# Switch_Matrix_CTRL.net
KiCad netlist of a schematic drawn in Altium Designer
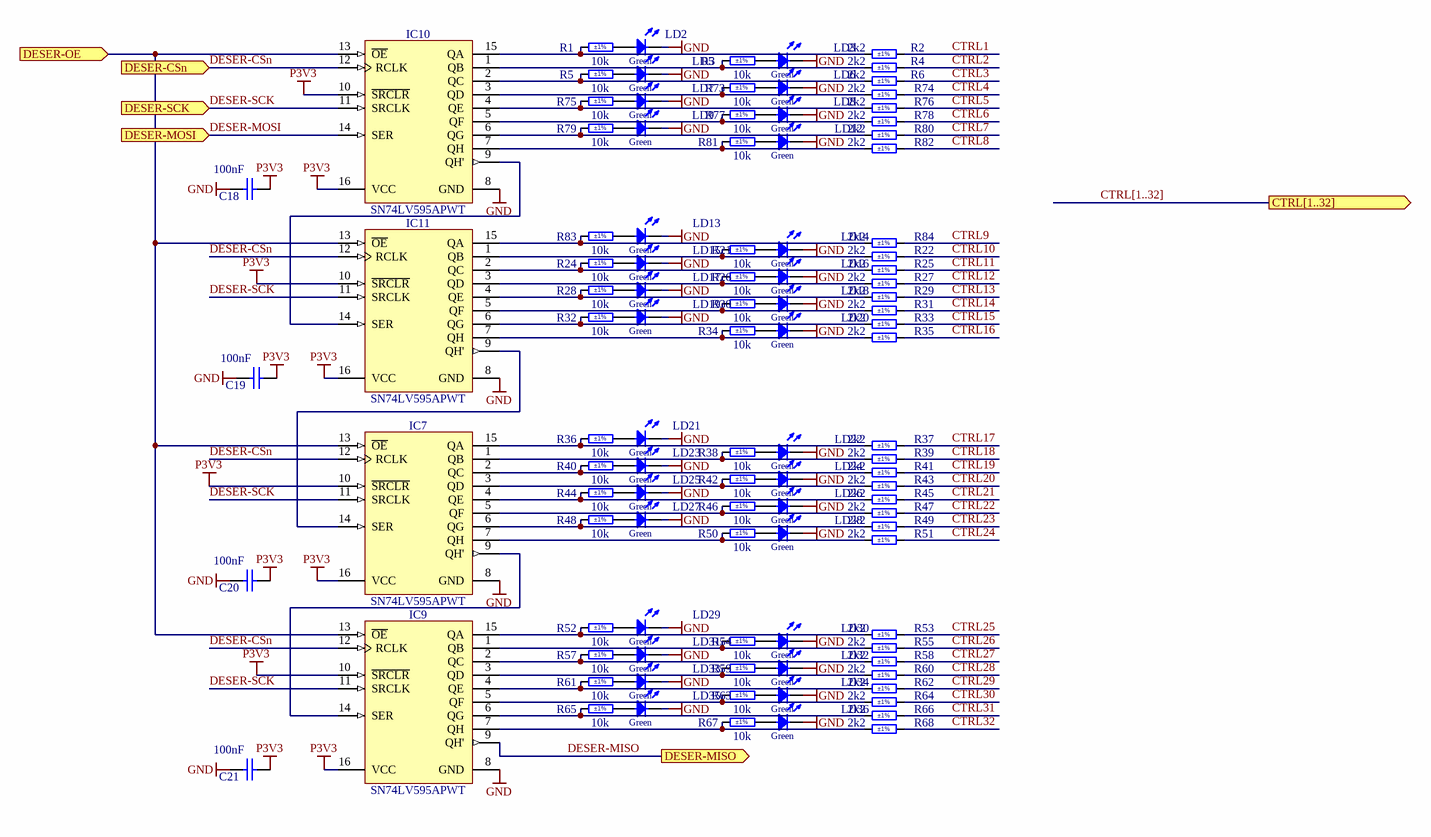
[diagram p0: Switch_Matrix_CTRL.schdoc]

(export (version "E")
  (design (tool "Eeschema 10.0.6"))
  (components
    (comp (ref "C18")
      (value "100nF")
      (footprint "CAPC1608X87N")
      (description "Non-polarised capacitor")
      (fields (field (name "PART NUMBER") "CC0603_100NF_50V_10%_X7R") (field (name "VOLTAGE") "50V"))
      (libsource (lib "Capacitors") (part "Capacitor - non polarized"))
    )
    (comp (ref "C19")
      (value "100nF")
      (footprint "CAPC1608X87N")
      (description "Non-polarised capacitor")
      (fields (field (name "PART NUMBER") "CC0603_100NF_50V_10%_X7R") (field (name "VOLTAGE") "50V"))
      (libsource (lib "Capacitors") (part "Capacitor - non polarized"))
    )
    (comp (ref "C20")
      (value "100nF")
      (footprint "CAPC1608X87N")
      (description "Non-polarised capacitor")
      (fields (field (name "PART NUMBER") "CC0603_100NF_50V_10%_X7R") (field (name "VOLTAGE") "50V"))
      (libsource (lib "Capacitors") (part "Capacitor - non polarized"))
    )
    (comp (ref "C21")
      (value "100nF")
      (footprint "CAPC1608X87N")
      (description "Non-polarised capacitor")
      (fields (field (name "PART NUMBER") "CC0603_100NF_50V_10%_X7R") (field (name "VOLTAGE") "50V"))
      (libsource (lib "Capacitors") (part "Capacitor - non polarized"))
    )
    (comp (ref "IC7")
      (value "SN74LV595APWT")
      (footprint "SOP65P640X120-16N")
      (description "8-Bit Shift Register With 3-State Output Register")
      (fields (field (name "MANUFACTURER") "TEXAS INSTRUMENTS"))
      (libsource (lib "ICs And Semiconductors") (part "74595"))
    )
    (comp (ref "IC9")
      (value "SN74LV595APWT")
      (footprint "SOP65P640X120-16N")
      (description "8-Bit Shift Register With 3-State Output Register")
      (fields (field (name "MANUFACTURER") "TEXAS INSTRUMENTS"))
      (libsource (lib "ICs And Semiconductors") (part "74595"))
    )
    (comp (ref "IC10")
      (value "SN74LV595APWT")
      (footprint "SOP65P640X120-16N")
      (description "8-Bit Shift Register With 3-State Output Register")
      (fields (field (name "MANUFACTURER") "TEXAS INSTRUMENTS"))
      (libsource (lib "ICs And Semiconductors") (part "74595"))
    )
    (comp (ref "IC11")
      (value "SN74LV595APWT")
      (footprint "SOP65P640X120-16N")
      (description "8-Bit Shift Register With 3-State Output Register")
      (fields (field (name "MANUFACTURER") "TEXAS INSTRUMENTS"))
      (libsource (lib "ICs And Semiconductors") (part "74595"))
    )
    (comp (ref "LD2")
      (value "Green")
      (footprint "LED_KINGBRIGHT_KP-1608CGCK")
      (description "LED Green 1C 2A")
      (fields
        (field (name "PART NUMBER") "LED_KINGBRIGHT_KP-1608CGCK")
        (field (name "MANUFACTURER") "KINGBRIGHT")
      )
      (libsource (lib "ICs And Semiconductors") (part "LED Green 1C 2A"))
    )
    (comp (ref "LD3")
      (value "Green")
      (footprint "LED_KINGBRIGHT_KP-1608CGCK")
      (description "LED Green 1C 2A")
      (fields
        (field (name "PART NUMBER") "LED_KINGBRIGHT_KP-1608CGCK")
        (field (name "MANUFACTURER") "KINGBRIGHT")
      )
      (libsource (lib "ICs And Semiconductors") (part "LED Green 1C 2A"))
    )
    (comp (ref "LD5")
      (value "Green")
      (footprint "LED_KINGBRIGHT_KP-1608CGCK")
      (description "LED Green 1C 2A")
      (fields
        (field (name "PART NUMBER") "LED_KINGBRIGHT_KP-1608CGCK")
        (field (name "MANUFACTURER") "KINGBRIGHT")
      )
      (libsource (lib "ICs And Semiconductors") (part "LED Green 1C 2A"))
    )
    (comp (ref "LD6")
      (value "Green")
      (footprint "LED_KINGBRIGHT_KP-1608CGCK")
      (description "LED Green 1C 2A")
      (fields
        (field (name "PART NUMBER") "LED_KINGBRIGHT_KP-1608CGCK")
        (field (name "MANUFACTURER") "KINGBRIGHT")
      )
      (libsource (lib "ICs And Semiconductors") (part "LED Green 1C 2A"))
    )
    (comp (ref "LD7")
      (value "Green")
      (footprint "LED_KINGBRIGHT_KP-1608CGCK")
      (description "LED Green 1C 2A")
      (fields
        (field (name "PART NUMBER") "LED_KINGBRIGHT_KP-1608CGCK")
        (field (name "MANUFACTURER") "KINGBRIGHT")
      )
      (libsource (lib "ICs And Semiconductors") (part "LED Green 1C 2A"))
    )
    (comp (ref "LD8")
      (value "Green")
      (footprint "LED_KINGBRIGHT_KP-1608CGCK")
      (description "LED Green 1C 2A")
      (fields
        (field (name "PART NUMBER") "LED_KINGBRIGHT_KP-1608CGCK")
        (field (name "MANUFACTURER") "KINGBRIGHT")
      )
      (libsource (lib "ICs And Semiconductors") (part "LED Green 1C 2A"))
    )
    (comp (ref "LD9")
      (value "Green")
      (footprint "LED_KINGBRIGHT_KP-1608CGCK")
      (description "LED Green 1C 2A")
      (fields
        (field (name "PART NUMBER") "LED_KINGBRIGHT_KP-1608CGCK")
        (field (name "MANUFACTURER") "KINGBRIGHT")
      )
      (libsource (lib "ICs And Semiconductors") (part "LED Green 1C 2A"))
    )
    (comp (ref "LD12")
      (value "Green")
      (footprint "LED_KINGBRIGHT_KP-1608CGCK")
      (description "LED Green 1C 2A")
      (fields
        (field (name "PART NUMBER") "LED_KINGBRIGHT_KP-1608CGCK")
        (field (name "MANUFACTURER") "KINGBRIGHT")
      )
      (libsource (lib "ICs And Semiconductors") (part "LED Green 1C 2A"))
    )
    (comp (ref "LD13")
      (value "Green")
      (footprint "LED_KINGBRIGHT_KP-1608CGCK")
      (description "LED Green 1C 2A")
      (fields
        (field (name "PART NUMBER") "LED_KINGBRIGHT_KP-1608CGCK")
        (field (name "MANUFACTURER") "KINGBRIGHT")
      )
      (libsource (lib "ICs And Semiconductors") (part "LED Green 1C 2A"))
    )
    (comp (ref "LD14")
      (value "Green")
      (footprint "LED_KINGBRIGHT_KP-1608CGCK")
      (description "LED Green 1C 2A")
      (fields
        (field (name "PART NUMBER") "LED_KINGBRIGHT_KP-1608CGCK")
        (field (name "MANUFACTURER") "KINGBRIGHT")
      )
      (libsource (lib "ICs And Semiconductors") (part "LED Green 1C 2A"))
    )
    (comp (ref "LD15")
      (value "Green")
      (footprint "LED_KINGBRIGHT_KP-1608CGCK")
      (description "LED Green 1C 2A")
      (fields
        (field (name "PART NUMBER") "LED_KINGBRIGHT_KP-1608CGCK")
        (field (name "MANUFACTURER") "KINGBRIGHT")
      )
      (libsource (lib "ICs And Semiconductors") (part "LED Green 1C 2A"))
    )
    (comp (ref "LD16")
      (value "Green")
      (footprint "LED_KINGBRIGHT_KP-1608CGCK")
      (description "LED Green 1C 2A")
      (fields
        (field (name "PART NUMBER") "LED_KINGBRIGHT_KP-1608CGCK")
        (field (name "MANUFACTURER") "KINGBRIGHT")
      )
      (libsource (lib "ICs And Semiconductors") (part "LED Green 1C 2A"))
    )
    (comp (ref "LD17")
      (value "Green")
      (footprint "LED_KINGBRIGHT_KP-1608CGCK")
      (description "LED Green 1C 2A")
      (fields
        (field (name "PART NUMBER") "LED_KINGBRIGHT_KP-1608CGCK")
        (field (name "MANUFACTURER") "KINGBRIGHT")
      )
      (libsource (lib "ICs And Semiconductors") (part "LED Green 1C 2A"))
    )
    (comp (ref "LD18")
      (value "Green")
      (footprint "LED_KINGBRIGHT_KP-1608CGCK")
      (description "LED Green 1C 2A")
      (fields
        (field (name "PART NUMBER") "LED_KINGBRIGHT_KP-1608CGCK")
        (field (name "MANUFACTURER") "KINGBRIGHT")
      )
      (libsource (lib "ICs And Semiconductors") (part "LED Green 1C 2A"))
    )
    (comp (ref "LD19")
      (value "Green")
      (footprint "LED_KINGBRIGHT_KP-1608CGCK")
      (description "LED Green 1C 2A")
      (fields
        (field (name "PART NUMBER") "LED_KINGBRIGHT_KP-1608CGCK")
        (field (name "MANUFACTURER") "KINGBRIGHT")
      )
      (libsource (lib "ICs And Semiconductors") (part "LED Green 1C 2A"))
    )
    (comp (ref "LD20")
      (value "Green")
      (footprint "LED_KINGBRIGHT_KP-1608CGCK")
      (description "LED Green 1C 2A")
      (fields
        (field (name "PART NUMBER") "LED_KINGBRIGHT_KP-1608CGCK")
        (field (name "MANUFACTURER") "KINGBRIGHT")
      )
      (libsource (lib "ICs And Semiconductors") (part "LED Green 1C 2A"))
    )
    (comp (ref "LD21")
      (value "Green")
      (footprint "LED_KINGBRIGHT_KP-1608CGCK")
      (description "LED Green 1C 2A")
      (fields
        (field (name "PART NUMBER") "LED_KINGBRIGHT_KP-1608CGCK")
        (field (name "MANUFACTURER") "KINGBRIGHT")
      )
      (libsource (lib "ICs And Semiconductors") (part "LED Green 1C 2A"))
    )
    (comp (ref "LD22")
      (value "Green")
      (footprint "LED_KINGBRIGHT_KP-1608CGCK")
      (description "LED Green 1C 2A")
      (fields
        (field (name "PART NUMBER") "LED_KINGBRIGHT_KP-1608CGCK")
        (field (name "MANUFACTURER") "KINGBRIGHT")
      )
      (libsource (lib "ICs And Semiconductors") (part "LED Green 1C 2A"))
    )
    (comp (ref "LD23")
      (value "Green")
      (footprint "LED_KINGBRIGHT_KP-1608CGCK")
      (description "LED Green 1C 2A")
      (fields
        (field (name "PART NUMBER") "LED_KINGBRIGHT_KP-1608CGCK")
        (field (name "MANUFACTURER") "KINGBRIGHT")
      )
      (libsource (lib "ICs And Semiconductors") (part "LED Green 1C 2A"))
    )
    (comp (ref "LD24")
      (value "Green")
      (footprint "LED_KINGBRIGHT_KP-1608CGCK")
      (description "LED Green 1C 2A")
      (fields
        (field (name "PART NUMBER") "LED_KINGBRIGHT_KP-1608CGCK")
        (field (name "MANUFACTURER") "KINGBRIGHT")
      )
      (libsource (lib "ICs And Semiconductors") (part "LED Green 1C 2A"))
    )
    (comp (ref "LD25")
      (value "Green")
      (footprint "LED_KINGBRIGHT_KP-1608CGCK")
      (description "LED Green 1C 2A")
      (fields
        (field (name "PART NUMBER") "LED_KINGBRIGHT_KP-1608CGCK")
        (field (name "MANUFACTURER") "KINGBRIGHT")
      )
      (libsource (lib "ICs And Semiconductors") (part "LED Green 1C 2A"))
    )
    (comp (ref "LD26")
      (value "Green")
      (footprint "LED_KINGBRIGHT_KP-1608CGCK")
      (description "LED Green 1C 2A")
      (fields
        (field (name "PART NUMBER") "LED_KINGBRIGHT_KP-1608CGCK")
        (field (name "MANUFACTURER") "KINGBRIGHT")
      )
      (libsource (lib "ICs And Semiconductors") (part "LED Green 1C 2A"))
    )
    (comp (ref "LD27")
      (value "Green")
      (footprint "LED_KINGBRIGHT_KP-1608CGCK")
      (description "LED Green 1C 2A")
      (fields
        (field (name "PART NUMBER") "LED_KINGBRIGHT_KP-1608CGCK")
        (field (name "MANUFACTURER") "KINGBRIGHT")
      )
      (libsource (lib "ICs And Semiconductors") (part "LED Green 1C 2A"))
    )
    (comp (ref "LD28")
      (value "Green")
      (footprint "LED_KINGBRIGHT_KP-1608CGCK")
      (description "LED Green 1C 2A")
      (fields
        (field (name "PART NUMBER") "LED_KINGBRIGHT_KP-1608CGCK")
        (field (name "MANUFACTURER") "KINGBRIGHT")
      )
      (libsource (lib "ICs And Semiconductors") (part "LED Green 1C 2A"))
    )
    (comp (ref "LD29")
      (value "Green")
      (footprint "LED_KINGBRIGHT_KP-1608CGCK")
      (description "LED Green 1C 2A")
      (fields
        (field (name "PART NUMBER") "LED_KINGBRIGHT_KP-1608CGCK")
        (field (name "MANUFACTURER") "KINGBRIGHT")
      )
      (libsource (lib "ICs And Semiconductors") (part "LED Green 1C 2A"))
    )
    (comp (ref "LD30")
      (value "Green")
      (footprint "LED_KINGBRIGHT_KP-1608CGCK")
      (description "LED Green 1C 2A")
      (fields
        (field (name "PART NUMBER") "LED_KINGBRIGHT_KP-1608CGCK")
        (field (name "MANUFACTURER") "KINGBRIGHT")
      )
      (libsource (lib "ICs And Semiconductors") (part "LED Green 1C 2A"))
    )
    (comp (ref "LD31")
      (value "Green")
      (footprint "LED_KINGBRIGHT_KP-1608CGCK")
      (description "LED Green 1C 2A")
      (fields
        (field (name "PART NUMBER") "LED_KINGBRIGHT_KP-1608CGCK")
        (field (name "MANUFACTURER") "KINGBRIGHT")
      )
      (libsource (lib "ICs And Semiconductors") (part "LED Green 1C 2A"))
    )
    (comp (ref "LD32")
      (value "Green")
      (footprint "LED_KINGBRIGHT_KP-1608CGCK")
      (description "LED Green 1C 2A")
      (fields
        (field (name "PART NUMBER") "LED_KINGBRIGHT_KP-1608CGCK")
        (field (name "MANUFACTURER") "KINGBRIGHT")
      )
      (libsource (lib "ICs And Semiconductors") (part "LED Green 1C 2A"))
    )
    (comp (ref "LD33")
      (value "Green")
      (footprint "LED_KINGBRIGHT_KP-1608CGCK")
      (description "LED Green 1C 2A")
      (fields
        (field (name "PART NUMBER") "LED_KINGBRIGHT_KP-1608CGCK")
        (field (name "MANUFACTURER") "KINGBRIGHT")
      )
      (libsource (lib "ICs And Semiconductors") (part "LED Green 1C 2A"))
    )
    (comp (ref "LD34")
      (value "Green")
      (footprint "LED_KINGBRIGHT_KP-1608CGCK")
      (description "LED Green 1C 2A")
      (fields
        (field (name "PART NUMBER") "LED_KINGBRIGHT_KP-1608CGCK")
        (field (name "MANUFACTURER") "KINGBRIGHT")
      )
      (libsource (lib "ICs And Semiconductors") (part "LED Green 1C 2A"))
    )
    (comp (ref "LD35")
      (value "Green")
      (footprint "LED_KINGBRIGHT_KP-1608CGCK")
      (description "LED Green 1C 2A")
      (fields
        (field (name "PART NUMBER") "LED_KINGBRIGHT_KP-1608CGCK")
        (field (name "MANUFACTURER") "KINGBRIGHT")
      )
      (libsource (lib "ICs And Semiconductors") (part "LED Green 1C 2A"))
    )
    (comp (ref "LD36")
      (value "Green")
      (footprint "LED_KINGBRIGHT_KP-1608CGCK")
      (description "LED Green 1C 2A")
      (fields
        (field (name "PART NUMBER") "LED_KINGBRIGHT_KP-1608CGCK")
        (field (name "MANUFACTURER") "KINGBRIGHT")
      )
      (libsource (lib "ICs And Semiconductors") (part "LED Green 1C 2A"))
    )
    (comp (ref "R1")
      (value "10k")
      (footprint "RESC1608X55N")
      (description "Resistor - 1%")
      (fields
        (field (name "TOLERANCE") "±1%")
        (field (name "PART NUMBER") "R0603_10K_1%_0.1W_100PPM")
        (field (name "POWER") "0.1W")
      )
      (libsource (lib "Resistors") (part "Resistor - 1%"))
    )
    (comp (ref "R2")
      (value "2k2")
      (footprint "RESC1608X55N")
      (description "Resistor - 1%")
      (fields
        (field (name "TOLERANCE") "±1%")
        (field (name "PART NUMBER") "R0603_2K2_1%_0.1W_100PPM")
        (field (name "POWER") "0.1W")
      )
      (libsource (lib "Resistors") (part "Resistor - 1%"))
    )
    (comp (ref "R3")
      (value "10k")
      (footprint "RESC1608X55N")
      (description "Resistor - 1%")
      (fields
        (field (name "TOLERANCE") "±1%")
        (field (name "PART NUMBER") "R0603_10K_1%_0.1W_100PPM")
        (field (name "POWER") "0.1W")
      )
      (libsource (lib "Resistors") (part "Resistor - 1%"))
    )
    (comp (ref "R4")
      (value "2k2")
      (footprint "RESC1608X55N")
      (description "Resistor - 1%")
      (fields
        (field (name "TOLERANCE") "±1%")
        (field (name "PART NUMBER") "R0603_2K2_1%_0.1W_100PPM")
        (field (name "POWER") "0.1W")
      )
      (libsource (lib "Resistors") (part "Resistor - 1%"))
    )
    (comp (ref "R5")
      (value "10k")
      (footprint "RESC1608X55N")
      (description "Resistor - 1%")
      (fields
        (field (name "TOLERANCE") "±1%")
        (field (name "PART NUMBER") "R0603_10K_1%_0.1W_100PPM")
        (field (name "POWER") "0.1W")
      )
      (libsource (lib "Resistors") (part "Resistor - 1%"))
    )
    (comp (ref "R6")
      (value "2k2")
      (footprint "RESC1608X55N")
      (description "Resistor - 1%")
      (fields
        (field (name "TOLERANCE") "±1%")
        (field (name "PART NUMBER") "R0603_2K2_1%_0.1W_100PPM")
        (field (name "POWER") "0.1W")
      )
      (libsource (lib "Resistors") (part "Resistor - 1%"))
    )
    (comp (ref "R21")
      (value "10k")
      (footprint "RESC1608X55N")
      (description "Resistor - 1%")
      (fields
        (field (name "TOLERANCE") "±1%")
        (field (name "PART NUMBER") "R0603_10K_1%_0.1W_100PPM")
        (field (name "POWER") "0.1W")
      )
      (libsource (lib "Resistors") (part "Resistor - 1%"))
    )
    (comp (ref "R22")
      (value "2k2")
      (footprint "RESC1608X55N")
      (description "Resistor - 1%")
      (fields
        (field (name "TOLERANCE") "±1%")
        (field (name "PART NUMBER") "R0603_2K2_1%_0.1W_100PPM")
        (field (name "POWER") "0.1W")
      )
      (libsource (lib "Resistors") (part "Resistor - 1%"))
    )
    (comp (ref "R24")
      (value "10k")
      (footprint "RESC1608X55N")
      (description "Resistor - 1%")
      (fields
        (field (name "TOLERANCE") "±1%")
        (field (name "PART NUMBER") "R0603_10K_1%_0.1W_100PPM")
        (field (name "POWER") "0.1W")
      )
      (libsource (lib "Resistors") (part "Resistor - 1%"))
    )
    (comp (ref "R25")
      (value "2k2")
      (footprint "RESC1608X55N")
      (description "Resistor - 1%")
      (fields
        (field (name "TOLERANCE") "±1%")
        (field (name "PART NUMBER") "R0603_2K2_1%_0.1W_100PPM")
        (field (name "POWER") "0.1W")
      )
      (libsource (lib "Resistors") (part "Resistor - 1%"))
    )
    (comp (ref "R26")
      (value "10k")
      (footprint "RESC1608X55N")
      (description "Resistor - 1%")
      (fields
        (field (name "TOLERANCE") "±1%")
        (field (name "PART NUMBER") "R0603_10K_1%_0.1W_100PPM")
        (field (name "POWER") "0.1W")
      )
      (libsource (lib "Resistors") (part "Resistor - 1%"))
    )
    (comp (ref "R27")
      (value "2k2")
      (footprint "RESC1608X55N")
      (description "Resistor - 1%")
      (fields
        (field (name "TOLERANCE") "±1%")
        (field (name "PART NUMBER") "R0603_2K2_1%_0.1W_100PPM")
        (field (name "POWER") "0.1W")
      )
      (libsource (lib "Resistors") (part "Resistor - 1%"))
    )
    (comp (ref "R28")
      (value "10k")
      (footprint "RESC1608X55N")
      (description "Resistor - 1%")
      (fields
        (field (name "TOLERANCE") "±1%")
        (field (name "PART NUMBER") "R0603_10K_1%_0.1W_100PPM")
        (field (name "POWER") "0.1W")
      )
      (libsource (lib "Resistors") (part "Resistor - 1%"))
    )
    (comp (ref "R29")
      (value "2k2")
      (footprint "RESC1608X55N")
      (description "Resistor - 1%")
      (fields
        (field (name "TOLERANCE") "±1%")
        (field (name "PART NUMBER") "R0603_2K2_1%_0.1W_100PPM")
        (field (name "POWER") "0.1W")
      )
      (libsource (lib "Resistors") (part "Resistor - 1%"))
    )
    (comp (ref "R30")
      (value "10k")
      (footprint "RESC1608X55N")
      (description "Resistor - 1%")
      (fields
        (field (name "TOLERANCE") "±1%")
        (field (name "PART NUMBER") "R0603_10K_1%_0.1W_100PPM")
        (field (name "POWER") "0.1W")
      )
      (libsource (lib "Resistors") (part "Resistor - 1%"))
    )
    (comp (ref "R31")
      (value "2k2")
      (footprint "RESC1608X55N")
      (description "Resistor - 1%")
      (fields
        (field (name "TOLERANCE") "±1%")
        (field (name "PART NUMBER") "R0603_2K2_1%_0.1W_100PPM")
        (field (name "POWER") "0.1W")
      )
      (libsource (lib "Resistors") (part "Resistor - 1%"))
    )
    (comp (ref "R32")
      (value "10k")
      (footprint "RESC1608X55N")
      (description "Resistor - 1%")
      (fields
        (field (name "TOLERANCE") "±1%")
        (field (name "PART NUMBER") "R0603_10K_1%_0.1W_100PPM")
        (field (name "POWER") "0.1W")
      )
      (libsource (lib "Resistors") (part "Resistor - 1%"))
    )
    (comp (ref "R33")
      (value "2k2")
      (footprint "RESC1608X55N")
      (description "Resistor - 1%")
      (fields
        (field (name "TOLERANCE") "±1%")
        (field (name "PART NUMBER") "R0603_2K2_1%_0.1W_100PPM")
        (field (name "POWER") "0.1W")
      )
      (libsource (lib "Resistors") (part "Resistor - 1%"))
    )
    (comp (ref "R34")
      (value "10k")
      (footprint "RESC1608X55N")
      (description "Resistor - 1%")
      (fields
        (field (name "TOLERANCE") "±1%")
        (field (name "PART NUMBER") "R0603_10K_1%_0.1W_100PPM")
        (field (name "POWER") "0.1W")
      )
      (libsource (lib "Resistors") (part "Resistor - 1%"))
    )
    (comp (ref "R35")
      (value "2k2")
      (footprint "RESC1608X55N")
      (description "Resistor - 1%")
      (fields
        (field (name "TOLERANCE") "±1%")
        (field (name "PART NUMBER") "R0603_2K2_1%_0.1W_100PPM")
        (field (name "POWER") "0.1W")
      )
      (libsource (lib "Resistors") (part "Resistor - 1%"))
    )
    (comp (ref "R36")
      (value "10k")
      (footprint "RESC1608X55N")
      (description "Resistor - 1%")
      (fields
        (field (name "TOLERANCE") "±1%")
        (field (name "PART NUMBER") "R0603_10K_1%_0.1W_100PPM")
        (field (name "POWER") "0.1W")
      )
      (libsource (lib "Resistors") (part "Resistor - 1%"))
    )
    (comp (ref "R37")
      (value "2k2")
      (footprint "RESC1608X55N")
      (description "Resistor - 1%")
      (fields
        (field (name "TOLERANCE") "±1%")
        (field (name "PART NUMBER") "R0603_2K2_1%_0.1W_100PPM")
        (field (name "POWER") "0.1W")
      )
      (libsource (lib "Resistors") (part "Resistor - 1%"))
    )
    (comp (ref "R38")
      (value "10k")
      (footprint "RESC1608X55N")
      (description "Resistor - 1%")
      (fields
        (field (name "TOLERANCE") "±1%")
        (field (name "PART NUMBER") "R0603_10K_1%_0.1W_100PPM")
        (field (name "POWER") "0.1W")
      )
      (libsource (lib "Resistors") (part "Resistor - 1%"))
    )
    (comp (ref "R39")
      (value "2k2")
      (footprint "RESC1608X55N")
      (description "Resistor - 1%")
      (fields
        (field (name "TOLERANCE") "±1%")
        (field (name "PART NUMBER") "R0603_2K2_1%_0.1W_100PPM")
        (field (name "POWER") "0.1W")
      )
      (libsource (lib "Resistors") (part "Resistor - 1%"))
    )
    (comp (ref "R40")
      (value "10k")
      (footprint "RESC1608X55N")
      (description "Resistor - 1%")
      (fields
        (field (name "TOLERANCE") "±1%")
        (field (name "PART NUMBER") "R0603_10K_1%_0.1W_100PPM")
        (field (name "POWER") "0.1W")
      )
      (libsource (lib "Resistors") (part "Resistor - 1%"))
    )
    (comp (ref "R41")
      (value "2k2")
      (footprint "RESC1608X55N")
      (description "Resistor - 1%")
      (fields
        (field (name "TOLERANCE") "±1%")
        (field (name "PART NUMBER") "R0603_2K2_1%_0.1W_100PPM")
        (field (name "POWER") "0.1W")
      )
      (libsource (lib "Resistors") (part "Resistor - 1%"))
    )
    (comp (ref "R42")
      (value "10k")
      (footprint "RESC1608X55N")
      (description "Resistor - 1%")
      (fields
        (field (name "TOLERANCE") "±1%")
        (field (name "PART NUMBER") "R0603_10K_1%_0.1W_100PPM")
        (field (name "POWER") "0.1W")
      )
      (libsource (lib "Resistors") (part "Resistor - 1%"))
    )
    (comp (ref "R43")
      (value "2k2")
      (footprint "RESC1608X55N")
      (description "Resistor - 1%")
      (fields
        (field (name "TOLERANCE") "±1%")
        (field (name "PART NUMBER") "R0603_2K2_1%_0.1W_100PPM")
        (field (name "POWER") "0.1W")
      )
      (libsource (lib "Resistors") (part "Resistor - 1%"))
    )
    (comp (ref "R44")
      (value "10k")
      (footprint "RESC1608X55N")
      (description "Resistor - 1%")
      (fields
        (field (name "TOLERANCE") "±1%")
        (field (name "PART NUMBER") "R0603_10K_1%_0.1W_100PPM")
        (field (name "POWER") "0.1W")
      )
      (libsource (lib "Resistors") (part "Resistor - 1%"))
    )
    (comp (ref "R45")
      (value "2k2")
      (footprint "RESC1608X55N")
      (description "Resistor - 1%")
      (fields
        (field (name "TOLERANCE") "±1%")
        (field (name "PART NUMBER") "R0603_2K2_1%_0.1W_100PPM")
        (field (name "POWER") "0.1W")
      )
      (libsource (lib "Resistors") (part "Resistor - 1%"))
    )
    (comp (ref "R46")
      (value "10k")
      (footprint "RESC1608X55N")
      (description "Resistor - 1%")
      (fields
        (field (name "TOLERANCE") "±1%")
        (field (name "PART NUMBER") "R0603_10K_1%_0.1W_100PPM")
        (field (name "POWER") "0.1W")
      )
      (libsource (lib "Resistors") (part "Resistor - 1%"))
    )
    (comp (ref "R47")
      (value "2k2")
      (footprint "RESC1608X55N")
      (description "Resistor - 1%")
      (fields
        (field (name "TOLERANCE") "±1%")
        (field (name "PART NUMBER") "R0603_2K2_1%_0.1W_100PPM")
        (field (name "POWER") "0.1W")
      )
      (libsource (lib "Resistors") (part "Resistor - 1%"))
    )
    (comp (ref "R48")
      (value "10k")
      (footprint "RESC1608X55N")
      (description "Resistor - 1%")
      (fields
        (field (name "TOLERANCE") "±1%")
        (field (name "PART NUMBER") "R0603_10K_1%_0.1W_100PPM")
        (field (name "POWER") "0.1W")
      )
      (libsource (lib "Resistors") (part "Resistor - 1%"))
    )
    (comp (ref "R49")
      (value "2k2")
      (footprint "RESC1608X55N")
      (description "Resistor - 1%")
      (fields
        (field (name "TOLERANCE") "±1%")
        (field (name "PART NUMBER") "R0603_2K2_1%_0.1W_100PPM")
        (field (name "POWER") "0.1W")
      )
      (libsource (lib "Resistors") (part "Resistor - 1%"))
    )
    (comp (ref "R50")
      (value "10k")
      (footprint "RESC1608X55N")
      (description "Resistor - 1%")
      (fields
        (field (name "TOLERANCE") "±1%")
        (field (name "PART NUMBER") "R0603_10K_1%_0.1W_100PPM")
        (field (name "POWER") "0.1W")
      )
      (libsource (lib "Resistors") (part "Resistor - 1%"))
    )
    (comp (ref "R51")
      (value "2k2")
      (footprint "RESC1608X55N")
      (description "Resistor - 1%")
      (fields
        (field (name "TOLERANCE") "±1%")
        (field (name "PART NUMBER") "R0603_2K2_1%_0.1W_100PPM")
        (field (name "POWER") "0.1W")
      )
      (libsource (lib "Resistors") (part "Resistor - 1%"))
    )
    (comp (ref "R52")
      (value "10k")
      (footprint "RESC1608X55N")
      (description "Resistor - 1%")
      (fields
        (field (name "TOLERANCE") "±1%")
        (field (name "PART NUMBER") "R0603_10K_1%_0.1W_100PPM")
        (field (name "POWER") "0.1W")
      )
      (libsource (lib "Resistors") (part "Resistor - 1%"))
    )
    (comp (ref "R53")
      (value "2k2")
      (footprint "RESC1608X55N")
      (description "Resistor - 1%")
      (fields
        (field (name "TOLERANCE") "±1%")
        (field (name "PART NUMBER") "R0603_2K2_1%_0.1W_100PPM")
        (field (name "POWER") "0.1W")
      )
      (libsource (lib "Resistors") (part "Resistor - 1%"))
    )
    (comp (ref "R54")
      (value "10k")
      (footprint "RESC1608X55N")
      (description "Resistor - 1%")
      (fields
        (field (name "TOLERANCE") "±1%")
        (field (name "PART NUMBER") "R0603_10K_1%_0.1W_100PPM")
        (field (name "POWER") "0.1W")
      )
      (libsource (lib "Resistors") (part "Resistor - 1%"))
    )
    (comp (ref "R55")
      (value "2k2")
      (footprint "RESC1608X55N")
      (description "Resistor - 1%")
      (fields
        (field (name "TOLERANCE") "±1%")
        (field (name "PART NUMBER") "R0603_2K2_1%_0.1W_100PPM")
        (field (name "POWER") "0.1W")
      )
      (libsource (lib "Resistors") (part "Resistor - 1%"))
    )
    (comp (ref "R57")
      (value "10k")
      (footprint "RESC1608X55N")
      (description "Resistor - 1%")
      (fields
        (field (name "TOLERANCE") "±1%")
        (field (name "PART NUMBER") "R0603_10K_1%_0.1W_100PPM")
        (field (name "POWER") "0.1W")
      )
      (libsource (lib "Resistors") (part "Resistor - 1%"))
    )
    (comp (ref "R58")
      (value "2k2")
      (footprint "RESC1608X55N")
      (description "Resistor - 1%")
      (fields
        (field (name "TOLERANCE") "±1%")
        (field (name "PART NUMBER") "R0603_2K2_1%_0.1W_100PPM")
        (field (name "POWER") "0.1W")
      )
      (libsource (lib "Resistors") (part "Resistor - 1%"))
    )
    (comp (ref "R59")
      (value "10k")
      (footprint "RESC1608X55N")
      (description "Resistor - 1%")
      (fields
        (field (name "TOLERANCE") "±1%")
        (field (name "PART NUMBER") "R0603_10K_1%_0.1W_100PPM")
        (field (name "POWER") "0.1W")
      )
      (libsource (lib "Resistors") (part "Resistor - 1%"))
    )
    (comp (ref "R60")
      (value "2k2")
      (footprint "RESC1608X55N")
      (description "Resistor - 1%")
      (fields
        (field (name "TOLERANCE") "±1%")
        (field (name "PART NUMBER") "R0603_2K2_1%_0.1W_100PPM")
        (field (name "POWER") "0.1W")
      )
      (libsource (lib "Resistors") (part "Resistor - 1%"))
    )
    (comp (ref "R61")
      (value "10k")
      (footprint "RESC1608X55N")
      (description "Resistor - 1%")
      (fields
        (field (name "TOLERANCE") "±1%")
        (field (name "PART NUMBER") "R0603_10K_1%_0.1W_100PPM")
        (field (name "POWER") "0.1W")
      )
      (libsource (lib "Resistors") (part "Resistor - 1%"))
    )
    (comp (ref "R62")
      (value "2k2")
      (footprint "RESC1608X55N")
      (description "Resistor - 1%")
      (fields
        (field (name "TOLERANCE") "±1%")
        (field (name "PART NUMBER") "R0603_2K2_1%_0.1W_100PPM")
        (field (name "POWER") "0.1W")
      )
      (libsource (lib "Resistors") (part "Resistor - 1%"))
    )
    (comp (ref "R63")
      (value "10k")
      (footprint "RESC1608X55N")
      (description "Resistor - 1%")
      (fields
        (field (name "TOLERANCE") "±1%")
        (field (name "PART NUMBER") "R0603_10K_1%_0.1W_100PPM")
        (field (name "POWER") "0.1W")
      )
      (libsource (lib "Resistors") (part "Resistor - 1%"))
    )
    (comp (ref "R64")
      (value "2k2")
      (footprint "RESC1608X55N")
      (description "Resistor - 1%")
      (fields
        (field (name "TOLERANCE") "±1%")
        (field (name "PART NUMBER") "R0603_2K2_1%_0.1W_100PPM")
        (field (name "POWER") "0.1W")
      )
      (libsource (lib "Resistors") (part "Resistor - 1%"))
    )
    (comp (ref "R65")
      (value "10k")
      (footprint "RESC1608X55N")
      (description "Resistor - 1%")
      (fields
        (field (name "TOLERANCE") "±1%")
        (field (name "PART NUMBER") "R0603_10K_1%_0.1W_100PPM")
        (field (name "POWER") "0.1W")
      )
      (libsource (lib "Resistors") (part "Resistor - 1%"))
    )
    (comp (ref "R66")
      (value "2k2")
      (footprint "RESC1608X55N")
      (description "Resistor - 1%")
      (fields
        (field (name "TOLERANCE") "±1%")
        (field (name "PART NUMBER") "R0603_2K2_1%_0.1W_100PPM")
        (field (name "POWER") "0.1W")
      )
      (libsource (lib "Resistors") (part "Resistor - 1%"))
    )
    (comp (ref "R67")
      (value "10k")
      (footprint "RESC1608X55N")
      (description "Resistor - 1%")
      (fields
        (field (name "TOLERANCE") "±1%")
        (field (name "PART NUMBER") "R0603_10K_1%_0.1W_100PPM")
        (field (name "POWER") "0.1W")
      )
      (libsource (lib "Resistors") (part "Resistor - 1%"))
    )
    (comp (ref "R68")
      (value "2k2")
      (footprint "RESC1608X55N")
      (description "Resistor - 1%")
      (fields
        (field (name "TOLERANCE") "±1%")
        (field (name "PART NUMBER") "R0603_2K2_1%_0.1W_100PPM")
        (field (name "POWER") "0.1W")
      )
      (libsource (lib "Resistors") (part "Resistor - 1%"))
    )
    (comp (ref "R73")
      (value "10k")
      (footprint "RESC1608X55N")
      (description "Resistor - 1%")
      (fields
        (field (name "TOLERANCE") "±1%")
        (field (name "PART NUMBER") "R0603_10K_1%_0.1W_100PPM")
        (field (name "POWER") "0.1W")
      )
      (libsource (lib "Resistors") (part "Resistor - 1%"))
    )
    (comp (ref "R74")
      (value "2k2")
      (footprint "RESC1608X55N")
      (description "Resistor - 1%")
      (fields
        (field (name "TOLERANCE") "±1%")
        (field (name "PART NUMBER") "R0603_2K2_1%_0.1W_100PPM")
        (field (name "POWER") "0.1W")
      )
      (libsource (lib "Resistors") (part "Resistor - 1%"))
    )
    (comp (ref "R75")
      (value "10k")
      (footprint "RESC1608X55N")
      (description "Resistor - 1%")
      (fields
        (field (name "TOLERANCE") "±1%")
        (field (name "PART NUMBER") "R0603_10K_1%_0.1W_100PPM")
        (field (name "POWER") "0.1W")
      )
      (libsource (lib "Resistors") (part "Resistor - 1%"))
    )
    (comp (ref "R76")
      (value "2k2")
      (footprint "RESC1608X55N")
      (description "Resistor - 1%")
      (fields
        (field (name "TOLERANCE") "±1%")
        (field (name "PART NUMBER") "R0603_2K2_1%_0.1W_100PPM")
        (field (name "POWER") "0.1W")
      )
      (libsource (lib "Resistors") (part "Resistor - 1%"))
    )
    (comp (ref "R77")
      (value "10k")
      (footprint "RESC1608X55N")
      (description "Resistor - 1%")
      (fields
        (field (name "TOLERANCE") "±1%")
        (field (name "PART NUMBER") "R0603_10K_1%_0.1W_100PPM")
        (field (name "POWER") "0.1W")
      )
      (libsource (lib "Resistors") (part "Resistor - 1%"))
    )
    (comp (ref "R78")
      (value "2k2")
      (footprint "RESC1608X55N")
      (description "Resistor - 1%")
      (fields
        (field (name "TOLERANCE") "±1%")
        (field (name "PART NUMBER") "R0603_2K2_1%_0.1W_100PPM")
        (field (name "POWER") "0.1W")
      )
      (libsource (lib "Resistors") (part "Resistor - 1%"))
    )
    (comp (ref "R79")
      (value "10k")
      (footprint "RESC1608X55N")
      (description "Resistor - 1%")
      (fields
        (field (name "TOLERANCE") "±1%")
        (field (name "PART NUMBER") "R0603_10K_1%_0.1W_100PPM")
        (field (name "POWER") "0.1W")
      )
      (libsource (lib "Resistors") (part "Resistor - 1%"))
    )
    (comp (ref "R80")
      (value "2k2")
      (footprint "RESC1608X55N")
      (description "Resistor - 1%")
      (fields
        (field (name "TOLERANCE") "±1%")
        (field (name "PART NUMBER") "R0603_2K2_1%_0.1W_100PPM")
        (field (name "POWER") "0.1W")
      )
      (libsource (lib "Resistors") (part "Resistor - 1%"))
    )
    (comp (ref "R81")
      (value "10k")
      (footprint "RESC1608X55N")
      (description "Resistor - 1%")
      (fields
        (field (name "TOLERANCE") "±1%")
        (field (name "PART NUMBER") "R0603_10K_1%_0.1W_100PPM")
        (field (name "POWER") "0.1W")
      )
      (libsource (lib "Resistors") (part "Resistor - 1%"))
    )
    (comp (ref "R82")
      (value "2k2")
      (footprint "RESC1608X55N")
      (description "Resistor - 1%")
      (fields
        (field (name "TOLERANCE") "±1%")
        (field (name "PART NUMBER") "R0603_2K2_1%_0.1W_100PPM")
        (field (name "POWER") "0.1W")
      )
      (libsource (lib "Resistors") (part "Resistor - 1%"))
    )
    (comp (ref "R83")
      (value "10k")
      (footprint "RESC1608X55N")
      (description "Resistor - 1%")
      (fields
        (field (name "TOLERANCE") "±1%")
        (field (name "PART NUMBER") "R0603_10K_1%_0.1W_100PPM")
        (field (name "POWER") "0.1W")
      )
      (libsource (lib "Resistors") (part "Resistor - 1%"))
    )
    (comp (ref "R84")
      (value "2k2")
      (footprint "RESC1608X55N")
      (description "Resistor - 1%")
      (fields
        (field (name "TOLERANCE") "±1%")
        (field (name "PART NUMBER") "R0603_2K2_1%_0.1W_100PPM")
        (field (name "POWER") "0.1W")
      )
      (libsource (lib "Resistors") (part "Resistor - 1%"))
    )
  )
  (nets
    (net (code "1") (name "/CTRL1") (class "Default")
      (node (ref "R2") (pin "2") (pinfunction "2_2") (pintype "passive"))
    )
    (net (code "2") (name "/CTRL2") (class "Default")
      (node (ref "R4") (pin "2") (pinfunction "2_2") (pintype "passive"))
    )
    (net (code "3") (name "/CTRL3") (class "Default")
      (node (ref "R6") (pin "2") (pinfunction "2_2") (pintype "passive"))
    )
    (net (code "4") (name "/CTRL4") (class "Default")
      (node (ref "R74") (pin "2") (pinfunction "2_2") (pintype "passive"))
    )
    (net (code "5") (name "/CTRL5") (class "Default")
      (node (ref "R76") (pin "2") (pinfunction "2_2") (pintype "passive"))
    )
    (net (code "6") (name "/CTRL6") (class "Default")
      (node (ref "R78") (pin "2") (pinfunction "2_2") (pintype "passive"))
    )
    (net (code "7") (name "/CTRL7") (class "Default")
      (node (ref "R80") (pin "2") (pinfunction "2_2") (pintype "passive"))
    )
    (net (code "8") (name "/CTRL8") (class "Default")
      (node (ref "R82") (pin "2") (pinfunction "2_2") (pintype "passive"))
    )
    (net (code "9") (name "/CTRL9") (class "Default")
      (node (ref "R84") (pin "2") (pinfunction "2_2") (pintype "passive"))
    )
    (net (code "10") (name "/CTRL10") (class "Default")
      (node (ref "R22") (pin "2") (pinfunction "2_2") (pintype "passive"))
    )
    (net (code "11") (name "/CTRL11") (class "Default")
      (node (ref "R25") (pin "2") (pinfunction "2_2") (pintype "passive"))
    )
    (net (code "12") (name "/CTRL12") (class "Default")
      (node (ref "R27") (pin "2") (pinfunction "2_2") (pintype "passive"))
    )
    (net (code "13") (name "/CTRL13") (class "Default")
      (node (ref "R29") (pin "2") (pinfunction "2_2") (pintype "passive"))
    )
    (net (code "14") (name "/CTRL14") (class "Default")
      (node (ref "R31") (pin "2") (pinfunction "2_2") (pintype "passive"))
    )
    (net (code "15") (name "/CTRL15") (class "Default")
      (node (ref "R33") (pin "2") (pinfunction "2_2") (pintype "passive"))
    )
    (net (code "16") (name "/CTRL16") (class "Default")
      (node (ref "R35") (pin "2") (pinfunction "2_2") (pintype "passive"))
    )
    (net (code "17") (name "/CTRL17") (class "Default")
      (node (ref "R37") (pin "2") (pinfunction "2_2") (pintype "passive"))
    )
    (net (code "18") (name "/CTRL18") (class "Default")
      (node (ref "R39") (pin "2") (pinfunction "2_2") (pintype "passive"))
    )
    (net (code "19") (name "/CTRL19") (class "Default")
      (node (ref "R41") (pin "2") (pinfunction "2_2") (pintype "passive"))
    )
    (net (code "20") (name "/CTRL20") (class "Default")
      (node (ref "R43") (pin "2") (pinfunction "2_2") (pintype "passive"))
    )
    (net (code "21") (name "/CTRL21") (class "Default")
      (node (ref "R45") (pin "2") (pinfunction "2_2") (pintype "passive"))
    )
    (net (code "22") (name "/CTRL22") (class "Default")
      (node (ref "R47") (pin "2") (pinfunction "2_2") (pintype "passive"))
    )
    (net (code "23") (name "/CTRL23") (class "Default")
      (node (ref "R49") (pin "2") (pinfunction "2_2") (pintype "passive"))
    )
    (net (code "24") (name "/CTRL24") (class "Default")
      (node (ref "R51") (pin "2") (pinfunction "2_2") (pintype "passive"))
    )
    (net (code "25") (name "/CTRL25") (class "Default")
      (node (ref "R53") (pin "2") (pinfunction "2_2") (pintype "passive"))
    )
    (net (code "26") (name "/CTRL26") (class "Default")
      (node (ref "R55") (pin "2") (pinfunction "2_2") (pintype "passive"))
    )
    (net (code "27") (name "/CTRL27") (class "Default")
      (node (ref "R58") (pin "2") (pinfunction "2_2") (pintype "passive"))
    )
    (net (code "28") (name "/CTRL28") (class "Default")
      (node (ref "R60") (pin "2") (pinfunction "2_2") (pintype "passive"))
    )
    (net (code "29") (name "/CTRL29") (class "Default")
      (node (ref "R62") (pin "2") (pinfunction "2_2") (pintype "passive"))
    )
    (net (code "30") (name "/CTRL30") (class "Default")
      (node (ref "R64") (pin "2") (pinfunction "2_2") (pintype "passive"))
    )
    (net (code "31") (name "/CTRL31") (class "Default")
      (node (ref "R66") (pin "2") (pinfunction "2_2") (pintype "passive"))
    )
    (net (code "32") (name "/CTRL32") (class "Default")
      (node (ref "R68") (pin "2") (pinfunction "2_2") (pintype "passive"))
    )
    (net (code "34") (name "/DESER-CSn") (class "Default")
      (node (ref "IC10") (pin "12") (pinfunction "RCLK_12") (pintype "input"))
      (node (ref "IC11") (pin "12") (pinfunction "RCLK_12") (pintype "input"))
      (node (ref "IC7") (pin "12") (pinfunction "RCLK_12") (pintype "input"))
      (node (ref "IC9") (pin "12") (pinfunction "RCLK_12") (pintype "input"))
    )
    (net (code "35") (name "/DESER-MISO") (class "Default")
      (node (ref "IC9") (pin "9") (pinfunction "QH'_9") (pintype "output"))
    )
    (net (code "36") (name "/DESER-MOSI") (class "Default")
      (node (ref "IC10") (pin "14") (pinfunction "SER_14") (pintype "input"))
    )
    (net (code "37") (name "/DESER-OE") (class "Default")
      (node (ref "IC10") (pin "13") (pinfunction "~{OE}_13") (pintype "input"))
      (node (ref "IC11") (pin "13") (pinfunction "~{OE}_13") (pintype "input"))
      (node (ref "IC7") (pin "13") (pinfunction "~{OE}_13") (pintype "input"))
      (node (ref "IC9") (pin "13") (pinfunction "~{OE}_13") (pintype "input"))
    )
    (net (code "38") (name "/DESER-SCK") (class "Default")
      (node (ref "IC10") (pin "11") (pinfunction "SRCLK_11") (pintype "input"))
      (node (ref "IC11") (pin "11") (pinfunction "SRCLK_11") (pintype "input"))
      (node (ref "IC7") (pin "11") (pinfunction "SRCLK_11") (pintype "input"))
      (node (ref "IC9") (pin "11") (pinfunction "SRCLK_11") (pintype "input"))
    )
    (net (code "39") (name "GND") (class "Default")
      (node (ref "C18") (pin "1") (pinfunction "1_1") (pintype "passive"))
      (node (ref "C19") (pin "1") (pinfunction "1_1") (pintype "passive"))
      (node (ref "C20") (pin "1") (pinfunction "1_1") (pintype "passive"))
      (node (ref "C21") (pin "1") (pinfunction "1_1") (pintype "passive"))
      (node (ref "IC10") (pin "8") (pinfunction "GND_8") (pintype "power_in"))
      (node (ref "IC11") (pin "8") (pinfunction "GND_8") (pintype "power_in"))
      (node (ref "IC7") (pin "8") (pinfunction "GND_8") (pintype "power_in"))
      (node (ref "IC9") (pin "8") (pinfunction "GND_8") (pintype "power_in"))
      (node (ref "LD12") (pin "1") (pinfunction "C_1") (pintype "passive"))
      (node (ref "LD13") (pin "1") (pinfunction "C_1") (pintype "passive"))
      (node (ref "LD14") (pin "1") (pinfunction "C_1") (pintype "passive"))
      (node (ref "LD15") (pin "1") (pinfunction "C_1") (pintype "passive"))
      (node (ref "LD16") (pin "1") (pinfunction "C_1") (pintype "passive"))
      (node (ref "LD17") (pin "1") (pinfunction "C_1") (pintype "passive"))
      (node (ref "LD18") (pin "1") (pinfunction "C_1") (pintype "passive"))
      (node (ref "LD19") (pin "1") (pinfunction "C_1") (pintype "passive"))
      (node (ref "LD2") (pin "1") (pinfunction "C_1") (pintype "passive"))
      (node (ref "LD20") (pin "1") (pinfunction "C_1") (pintype "passive"))
      (node (ref "LD21") (pin "1") (pinfunction "C_1") (pintype "passive"))
      (node (ref "LD22") (pin "1") (pinfunction "C_1") (pintype "passive"))
      (node (ref "LD23") (pin "1") (pinfunction "C_1") (pintype "passive"))
      (node (ref "LD24") (pin "1") (pinfunction "C_1") (pintype "passive"))
      (node (ref "LD25") (pin "1") (pinfunction "C_1") (pintype "passive"))
      (node (ref "LD26") (pin "1") (pinfunction "C_1") (pintype "passive"))
      (node (ref "LD27") (pin "1") (pinfunction "C_1") (pintype "passive"))
      (node (ref "LD28") (pin "1") (pinfunction "C_1") (pintype "passive"))
      (node (ref "LD29") (pin "1") (pinfunction "C_1") (pintype "passive"))
      (node (ref "LD3") (pin "1") (pinfunction "C_1") (pintype "passive"))
      (node (ref "LD30") (pin "1") (pinfunction "C_1") (pintype "passive"))
      (node (ref "LD31") (pin "1") (pinfunction "C_1") (pintype "passive"))
      (node (ref "LD32") (pin "1") (pinfunction "C_1") (pintype "passive"))
      (node (ref "LD33") (pin "1") (pinfunction "C_1") (pintype "passive"))
      (node (ref "LD34") (pin "1") (pinfunction "C_1") (pintype "passive"))
      (node (ref "LD35") (pin "1") (pinfunction "C_1") (pintype "passive"))
      (node (ref "LD36") (pin "1") (pinfunction "C_1") (pintype "passive"))
      (node (ref "LD5") (pin "1") (pinfunction "C_1") (pintype "passive"))
      (node (ref "LD6") (pin "1") (pinfunction "C_1") (pintype "passive"))
      (node (ref "LD7") (pin "1") (pinfunction "C_1") (pintype "passive"))
      (node (ref "LD8") (pin "1") (pinfunction "C_1") (pintype "passive"))
      (node (ref "LD9") (pin "1") (pinfunction "C_1") (pintype "passive"))
    )
    (net (code "40") (name "Net-(IC7-QA)") (class "Default")
      (node (ref "IC7") (pin "15") (pinfunction "QA_15") (pintype "tri_state"))
      (node (ref "R36") (pin "1") (pinfunction "1_1") (pintype "passive"))
      (node (ref "R37") (pin "1") (pinfunction "1_1") (pintype "passive"))
    )
    (net (code "41") (name "Net-(IC7-QB)") (class "Default")
      (node (ref "IC7") (pin "1") (pinfunction "QB_1") (pintype "tri_state"))
      (node (ref "R38") (pin "1") (pinfunction "1_1") (pintype "passive"))
      (node (ref "R39") (pin "1") (pinfunction "1_1") (pintype "passive"))
    )
    (net (code "42") (name "Net-(IC7-QC)") (class "Default")
      (node (ref "IC7") (pin "2") (pinfunction "QC_2") (pintype "tri_state"))
      (node (ref "R40") (pin "1") (pinfunction "1_1") (pintype "passive"))
      (node (ref "R41") (pin "1") (pinfunction "1_1") (pintype "passive"))
    )
    (net (code "43") (name "Net-(IC7-QD)") (class "Default")
      (node (ref "IC7") (pin "3") (pinfunction "QD_3") (pintype "tri_state"))
      (node (ref "R42") (pin "1") (pinfunction "1_1") (pintype "passive"))
      (node (ref "R43") (pin "1") (pinfunction "1_1") (pintype "passive"))
    )
    (net (code "44") (name "Net-(IC7-QE)") (class "Default")
      (node (ref "IC7") (pin "4") (pinfunction "QE_4") (pintype "tri_state"))
      (node (ref "R44") (pin "1") (pinfunction "1_1") (pintype "passive"))
      (node (ref "R45") (pin "1") (pinfunction "1_1") (pintype "passive"))
    )
    (net (code "45") (name "Net-(IC7-QF)") (class "Default")
      (node (ref "IC7") (pin "5") (pinfunction "QF_5") (pintype "tri_state"))
      (node (ref "R46") (pin "1") (pinfunction "1_1") (pintype "passive"))
      (node (ref "R47") (pin "1") (pinfunction "1_1") (pintype "passive"))
    )
    (net (code "46") (name "Net-(IC7-QG)") (class "Default")
      (node (ref "IC7") (pin "6") (pinfunction "QG_6") (pintype "tri_state"))
      (node (ref "R48") (pin "1") (pinfunction "1_1") (pintype "passive"))
      (node (ref "R49") (pin "1") (pinfunction "1_1") (pintype "passive"))
    )
    (net (code "47") (name "Net-(IC7-QH')") (class "Default")
      (node (ref "IC7") (pin "9") (pinfunction "QH'_9") (pintype "output"))
      (node (ref "IC9") (pin "14") (pinfunction "SER_14") (pintype "input"))
    )
    (net (code "48") (name "Net-(IC7-QH)") (class "Default")
      (node (ref "IC7") (pin "7") (pinfunction "QH_7") (pintype "tri_state"))
      (node (ref "R50") (pin "1") (pinfunction "1_1") (pintype "passive"))
      (node (ref "R51") (pin "1") (pinfunction "1_1") (pintype "passive"))
    )
    (net (code "49") (name "Net-(IC9-QA)") (class "Default")
      (node (ref "IC9") (pin "15") (pinfunction "QA_15") (pintype "tri_state"))
      (node (ref "R52") (pin "1") (pinfunction "1_1") (pintype "passive"))
      (node (ref "R53") (pin "1") (pinfunction "1_1") (pintype "passive"))
    )
    (net (code "50") (name "Net-(IC9-QB)") (class "Default")
      (node (ref "IC9") (pin "1") (pinfunction "QB_1") (pintype "tri_state"))
      (node (ref "R54") (pin "1") (pinfunction "1_1") (pintype "passive"))
      (node (ref "R55") (pin "1") (pinfunction "1_1") (pintype "passive"))
    )
    (net (code "51") (name "Net-(IC9-QC)") (class "Default")
      (node (ref "IC9") (pin "2") (pinfunction "QC_2") (pintype "tri_state"))
      (node (ref "R57") (pin "1") (pinfunction "1_1") (pintype "passive"))
      (node (ref "R58") (pin "1") (pinfunction "1_1") (pintype "passive"))
    )
    (net (code "52") (name "Net-(IC9-QD)") (class "Default")
      (node (ref "IC9") (pin "3") (pinfunction "QD_3") (pintype "tri_state"))
      (node (ref "R59") (pin "1") (pinfunction "1_1") (pintype "passive"))
      (node (ref "R60") (pin "1") (pinfunction "1_1") (pintype "passive"))
    )
    (net (code "53") (name "Net-(IC9-QE)") (class "Default")
      (node (ref "IC9") (pin "4") (pinfunction "QE_4") (pintype "tri_state"))
      (node (ref "R61") (pin "1") (pinfunction "1_1") (pintype "passive"))
      (node (ref "R62") (pin "1") (pinfunction "1_1") (pintype "passive"))
    )
    (net (code "54") (name "Net-(IC9-QF)") (class "Default")
      (node (ref "IC9") (pin "5") (pinfunction "QF_5") (pintype "tri_state"))
      (node (ref "R63") (pin "1") (pinfunction "1_1") (pintype "passive"))
      (node (ref "R64") (pin "1") (pinfunction "1_1") (pintype "passive"))
    )
    (net (code "55") (name "Net-(IC9-QG)") (class "Default")
      (node (ref "IC9") (pin "6") (pinfunction "QG_6") (pintype "tri_state"))
      (node (ref "R65") (pin "1") (pinfunction "1_1") (pintype "passive"))
      (node (ref "R66") (pin "1") (pinfunction "1_1") (pintype "passive"))
    )
    (net (code "56") (name "Net-(IC9-QH)") (class "Default")
      (node (ref "IC9") (pin "7") (pinfunction "QH_7") (pintype "tri_state"))
      (node (ref "R67") (pin "1") (pinfunction "1_1") (pintype "passive"))
      (node (ref "R68") (pin "1") (pinfunction "1_1") (pintype "passive"))
    )
    (net (code "57") (name "Net-(IC10-QA)") (class "Default")
      (node (ref "IC10") (pin "15") (pinfunction "QA_15") (pintype "tri_state"))
      (node (ref "R1") (pin "1") (pinfunction "1_1") (pintype "passive"))
      (node (ref "R2") (pin "1") (pinfunction "1_1") (pintype "passive"))
    )
    (net (code "58") (name "Net-(IC10-QB)") (class "Default")
      (node (ref "IC10") (pin "1") (pinfunction "QB_1") (pintype "tri_state"))
      (node (ref "R3") (pin "1") (pinfunction "1_1") (pintype "passive"))
      (node (ref "R4") (pin "1") (pinfunction "1_1") (pintype "passive"))
    )
    (net (code "59") (name "Net-(IC10-QC)") (class "Default")
      (node (ref "IC10") (pin "2") (pinfunction "QC_2") (pintype "tri_state"))
      (node (ref "R5") (pin "1") (pinfunction "1_1") (pintype "passive"))
      (node (ref "R6") (pin "1") (pinfunction "1_1") (pintype "passive"))
    )
    (net (code "60") (name "Net-(IC10-QD)") (class "Default")
      (node (ref "IC10") (pin "3") (pinfunction "QD_3") (pintype "tri_state"))
      (node (ref "R73") (pin "1") (pinfunction "1_1") (pintype "passive"))
      (node (ref "R74") (pin "1") (pinfunction "1_1") (pintype "passive"))
    )
    (net (code "61") (name "Net-(IC10-QE)") (class "Default")
      (node (ref "IC10") (pin "4") (pinfunction "QE_4") (pintype "tri_state"))
      (node (ref "R75") (pin "1") (pinfunction "1_1") (pintype "passive"))
      (node (ref "R76") (pin "1") (pinfunction "1_1") (pintype "passive"))
    )
    (net (code "62") (name "Net-(IC10-QF)") (class "Default")
      (node (ref "IC10") (pin "5") (pinfunction "QF_5") (pintype "tri_state"))
      (node (ref "R77") (pin "1") (pinfunction "1_1") (pintype "passive"))
      (node (ref "R78") (pin "1") (pinfunction "1_1") (pintype "passive"))
    )
    (net (code "63") (name "Net-(IC10-QG)") (class "Default")
      (node (ref "IC10") (pin "6") (pinfunction "QG_6") (pintype "tri_state"))
      (node (ref "R79") (pin "1") (pinfunction "1_1") (pintype "passive"))
      (node (ref "R80") (pin "1") (pinfunction "1_1") (pintype "passive"))
    )
    (net (code "64") (name "Net-(IC10-QH')") (class "Default")
      (node (ref "IC10") (pin "9") (pinfunction "QH'_9") (pintype "output"))
      (node (ref "IC11") (pin "14") (pinfunction "SER_14") (pintype "input"))
    )
    (net (code "65") (name "Net-(IC10-QH)") (class "Default")
      (node (ref "IC10") (pin "7") (pinfunction "QH_7") (pintype "tri_state"))
      (node (ref "R81") (pin "1") (pinfunction "1_1") (pintype "passive"))
      (node (ref "R82") (pin "1") (pinfunction "1_1") (pintype "passive"))
    )
    (net (code "66") (name "Net-(IC11-QA)") (class "Default")
      (node (ref "IC11") (pin "15") (pinfunction "QA_15") (pintype "tri_state"))
      (node (ref "R83") (pin "1") (pinfunction "1_1") (pintype "passive"))
      (node (ref "R84") (pin "1") (pinfunction "1_1") (pintype "passive"))
    )
    (net (code "67") (name "Net-(IC11-QB)") (class "Default")
      (node (ref "IC11") (pin "1") (pinfunction "QB_1") (pintype "tri_state"))
      (node (ref "R21") (pin "1") (pinfunction "1_1") (pintype "passive"))
      (node (ref "R22") (pin "1") (pinfunction "1_1") (pintype "passive"))
    )
    (net (code "68") (name "Net-(IC11-QC)") (class "Default")
      (node (ref "IC11") (pin "2") (pinfunction "QC_2") (pintype "tri_state"))
      (node (ref "R24") (pin "1") (pinfunction "1_1") (pintype "passive"))
      (node (ref "R25") (pin "1") (pinfunction "1_1") (pintype "passive"))
    )
    (net (code "69") (name "Net-(IC11-QD)") (class "Default")
      (node (ref "IC11") (pin "3") (pinfunction "QD_3") (pintype "tri_state"))
      (node (ref "R26") (pin "1") (pinfunction "1_1") (pintype "passive"))
      (node (ref "R27") (pin "1") (pinfunction "1_1") (pintype "passive"))
    )
    (net (code "70") (name "Net-(IC11-QE)") (class "Default")
      (node (ref "IC11") (pin "4") (pinfunction "QE_4") (pintype "tri_state"))
      (node (ref "R28") (pin "1") (pinfunction "1_1") (pintype "passive"))
      (node (ref "R29") (pin "1") (pinfunction "1_1") (pintype "passive"))
    )
    (net (code "71") (name "Net-(IC11-QF)") (class "Default")
      (node (ref "IC11") (pin "5") (pinfunction "QF_5") (pintype "tri_state"))
      (node (ref "R30") (pin "1") (pinfunction "1_1") (pintype "passive"))
      (node (ref "R31") (pin "1") (pinfunction "1_1") (pintype "passive"))
    )
    (net (code "72") (name "Net-(IC11-QG)") (class "Default")
      (node (ref "IC11") (pin "6") (pinfunction "QG_6") (pintype "tri_state"))
      (node (ref "R32") (pin "1") (pinfunction "1_1") (pintype "passive"))
      (node (ref "R33") (pin "1") (pinfunction "1_1") (pintype "passive"))
    )
    (net (code "73") (name "Net-(IC11-QH')") (class "Default")
      (node (ref "IC11") (pin "9") (pinfunction "QH'_9") (pintype "output"))
      (node (ref "IC7") (pin "14") (pinfunction "SER_14") (pintype "input"))
    )
    (net (code "74") (name "Net-(IC11-QH)") (class "Default")
      (node (ref "IC11") (pin "7") (pinfunction "QH_7") (pintype "tri_state"))
      (node (ref "R34") (pin "1") (pinfunction "1_1") (pintype "passive"))
      (node (ref "R35") (pin "1") (pinfunction "1_1") (pintype "passive"))
    )
    (net (code "75") (name "Net-(LD2-A)") (class "Default")
      (node (ref "LD2") (pin "2") (pinfunction "A_2") (pintype "passive"))
      (node (ref "R1") (pin "2") (pinfunction "2_2") (pintype "passive"))
    )
    (net (code "76") (name "Net-(LD3-A)") (class "Default")
      (node (ref "LD3") (pin "2") (pinfunction "A_2") (pintype "passive"))
      (node (ref "R3") (pin "2") (pinfunction "2_2") (pintype "passive"))
    )
    (net (code "77") (name "Net-(LD5-A)") (class "Default")
      (node (ref "LD5") (pin "2") (pinfunction "A_2") (pintype "passive"))
      (node (ref "R5") (pin "2") (pinfunction "2_2") (pintype "passive"))
    )
    (net (code "78") (name "Net-(LD6-A)") (class "Default")
      (node (ref "LD6") (pin "2") (pinfunction "A_2") (pintype "passive"))
      (node (ref "R73") (pin "2") (pinfunction "2_2") (pintype "passive"))
    )
    (net (code "79") (name "Net-(LD7-A)") (class "Default")
      (node (ref "LD7") (pin "2") (pinfunction "A_2") (pintype "passive"))
      (node (ref "R75") (pin "2") (pinfunction "2_2") (pintype "passive"))
    )
    (net (code "80") (name "Net-(LD8-A)") (class "Default")
      (node (ref "LD8") (pin "2") (pinfunction "A_2") (pintype "passive"))
      (node (ref "R77") (pin "2") (pinfunction "2_2") (pintype "passive"))
    )
    (net (code "81") (name "Net-(LD9-A)") (class "Default")
      (node (ref "LD9") (pin "2") (pinfunction "A_2") (pintype "passive"))
      (node (ref "R79") (pin "2") (pinfunction "2_2") (pintype "passive"))
    )
    (net (code "82") (name "Net-(LD12-A)") (class "Default")
      (node (ref "LD12") (pin "2") (pinfunction "A_2") (pintype "passive"))
      (node (ref "R81") (pin "2") (pinfunction "2_2") (pintype "passive"))
    )
    (net (code "83") (name "Net-(LD13-A)") (class "Default")
      (node (ref "LD13") (pin "2") (pinfunction "A_2") (pintype "passive"))
      (node (ref "R83") (pin "2") (pinfunction "2_2") (pintype "passive"))
    )
    (net (code "84") (name "Net-(LD14-A)") (class "Default")
      (node (ref "LD14") (pin "2") (pinfunction "A_2") (pintype "passive"))
      (node (ref "R21") (pin "2") (pinfunction "2_2") (pintype "passive"))
    )
    (net (code "85") (name "Net-(LD15-A)") (class "Default")
      (node (ref "LD15") (pin "2") (pinfunction "A_2") (pintype "passive"))
      (node (ref "R24") (pin "2") (pinfunction "2_2") (pintype "passive"))
    )
    (net (code "86") (name "Net-(LD16-A)") (class "Default")
      (node (ref "LD16") (pin "2") (pinfunction "A_2") (pintype "passive"))
      (node (ref "R26") (pin "2") (pinfunction "2_2") (pintype "passive"))
    )
    (net (code "87") (name "Net-(LD17-A)") (class "Default")
      (node (ref "LD17") (pin "2") (pinfunction "A_2") (pintype "passive"))
      (node (ref "R28") (pin "2") (pinfunction "2_2") (pintype "passive"))
    )
    (net (code "88") (name "Net-(LD18-A)") (class "Default")
      (node (ref "LD18") (pin "2") (pinfunction "A_2") (pintype "passive"))
      (node (ref "R30") (pin "2") (pinfunction "2_2") (pintype "passive"))
    )
    (net (code "89") (name "Net-(LD19-A)") (class "Default")
      (node (ref "LD19") (pin "2") (pinfunction "A_2") (pintype "passive"))
      (node (ref "R32") (pin "2") (pinfunction "2_2") (pintype "passive"))
    )
    (net (code "90") (name "Net-(LD20-A)") (class "Default")
      (node (ref "LD20") (pin "2") (pinfunction "A_2") (pintype "passive"))
      (node (ref "R34") (pin "2") (pinfunction "2_2") (pintype "passive"))
    )
    (net (code "91") (name "Net-(LD21-A)") (class "Default")
      (node (ref "LD21") (pin "2") (pinfunction "A_2") (pintype "passive"))
      (node (ref "R36") (pin "2") (pinfunction "2_2") (pintype "passive"))
    )
    (net (code "92") (name "Net-(LD22-A)") (class "Default")
      (node (ref "LD22") (pin "2") (pinfunction "A_2") (pintype "passive"))
      (node (ref "R38") (pin "2") (pinfunction "2_2") (pintype "passive"))
    )
    (net (code "93") (name "Net-(LD23-A)") (class "Default")
      (node (ref "LD23") (pin "2") (pinfunction "A_2") (pintype "passive"))
      (node (ref "R40") (pin "2") (pinfunction "2_2") (pintype "passive"))
    )
    (net (code "94") (name "Net-(LD24-A)") (class "Default")
      (node (ref "LD24") (pin "2") (pinfunction "A_2") (pintype "passive"))
      (node (ref "R42") (pin "2") (pinfunction "2_2") (pintype "passive"))
    )
    (net (code "95") (name "Net-(LD25-A)") (class "Default")
      (node (ref "LD25") (pin "2") (pinfunction "A_2") (pintype "passive"))
      (node (ref "R44") (pin "2") (pinfunction "2_2") (pintype "passive"))
    )
    (net (code "96") (name "Net-(LD26-A)") (class "Default")
      (node (ref "LD26") (pin "2") (pinfunction "A_2") (pintype "passive"))
      (node (ref "R46") (pin "2") (pinfunction "2_2") (pintype "passive"))
    )
    (net (code "97") (name "Net-(LD27-A)") (class "Default")
      (node (ref "LD27") (pin "2") (pinfunction "A_2") (pintype "passive"))
      (node (ref "R48") (pin "2") (pinfunction "2_2") (pintype "passive"))
    )
    (net (code "98") (name "Net-(LD28-A)") (class "Default")
      (node (ref "LD28") (pin "2") (pinfunction "A_2") (pintype "passive"))
      (node (ref "R50") (pin "2") (pinfunction "2_2") (pintype "passive"))
    )
    (net (code "99") (name "Net-(LD29-A)") (class "Default")
      (node (ref "LD29") (pin "2") (pinfunction "A_2") (pintype "passive"))
      (node (ref "R52") (pin "2") (pinfunction "2_2") (pintype "passive"))
    )
    (net (code "100") (name "Net-(LD30-A)") (class "Default")
      (node (ref "LD30") (pin "2") (pinfunction "A_2") (pintype "passive"))
      (node (ref "R54") (pin "2") (pinfunction "2_2") (pintype "passive"))
    )
    (net (code "101") (name "Net-(LD31-A)") (class "Default")
      (node (ref "LD31") (pin "2") (pinfunction "A_2") (pintype "passive"))
      (node (ref "R57") (pin "2") (pinfunction "2_2") (pintype "passive"))
    )
    (net (code "102") (name "Net-(LD32-A)") (class "Default")
      (node (ref "LD32") (pin "2") (pinfunction "A_2") (pintype "passive"))
      (node (ref "R59") (pin "2") (pinfunction "2_2") (pintype "passive"))
    )
    (net (code "103") (name "Net-(LD33-A)") (class "Default")
      (node (ref "LD33") (pin "2") (pinfunction "A_2") (pintype "passive"))
      (node (ref "R61") (pin "2") (pinfunction "2_2") (pintype "passive"))
    )
    (net (code "104") (name "Net-(LD34-A)") (class "Default")
      (node (ref "LD34") (pin "2") (pinfunction "A_2") (pintype "passive"))
      (node (ref "R63") (pin "2") (pinfunction "2_2") (pintype "passive"))
    )
    (net (code "105") (name "Net-(LD35-A)") (class "Default")
      (node (ref "LD35") (pin "2") (pinfunction "A_2") (pintype "passive"))
      (node (ref "R65") (pin "2") (pinfunction "2_2") (pintype "passive"))
    )
    (net (code "106") (name "Net-(LD36-A)") (class "Default")
      (node (ref "LD36") (pin "2") (pinfunction "A_2") (pintype "passive"))
      (node (ref "R67") (pin "2") (pinfunction "2_2") (pintype "passive"))
    )
    (net (code "107") (name "P3V3") (class "Default")
      (node (ref "C18") (pin "2") (pinfunction "2_2") (pintype "passive"))
      (node (ref "C19") (pin "2") (pinfunction "2_2") (pintype "passive"))
      (node (ref "C20") (pin "2") (pinfunction "2_2") (pintype "passive"))
      (node (ref "C21") (pin "2") (pinfunction "2_2") (pintype "passive"))
      (node (ref "IC10") (pin "10") (pinfunction "~{SRCLR}_10") (pintype "input"))
      (node (ref "IC10") (pin "16") (pinfunction "VCC_16") (pintype "power_in"))
      (node (ref "IC11") (pin "10") (pinfunction "~{SRCLR}_10") (pintype "input"))
      (node (ref "IC11") (pin "16") (pinfunction "VCC_16") (pintype "power_in"))
      (node (ref "IC7") (pin "10") (pinfunction "~{SRCLR}_10") (pintype "input"))
      (node (ref "IC7") (pin "16") (pinfunction "VCC_16") (pintype "power_in"))
      (node (ref "IC9") (pin "10") (pinfunction "~{SRCLR}_10") (pintype "input"))
      (node (ref "IC9") (pin "16") (pinfunction "VCC_16") (pintype "power_in"))
    )
  )
)
